# Sheet1.net
KiCad netlist of a schematic drawn in Altium Designer
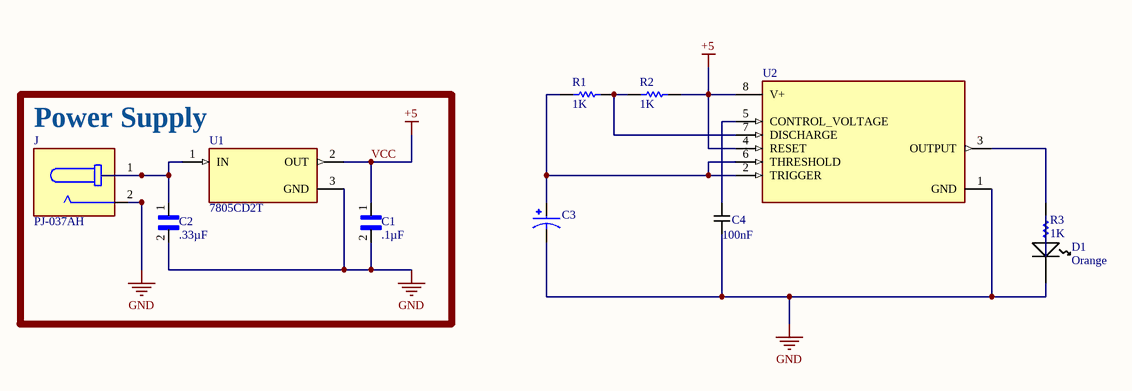
[diagram p0: Sheet1.SchDoc]

(export (version "E")
  (design (tool "Eeschema 10.0.6"))
  (components
    (comp (ref "C1")
      (value ".1µF")
      (footprint "CAPC3216X190N")
      (description "SMD Multilayer Ceramic Capacitor, GRM Series, 220 F, 20%, X5R, 6.3 V, 1206 [3216 Metric]")
      (fields (field (name "DIGI-KEY_PART_NUMBER") "490-13970-1-ND") (field (name "MP") "GRM31CR60J227ME11L"))
      (libsource (lib "GRM31CR60J227ME11L") (part "GRM31CR60J227ME11L"))
    )
    (comp (ref "C2")
      (value ".33µF")
      (footprint "CAPC3216X190N")
      (description "SMD Multilayer Ceramic Capacitor, GRM Series, 220 F, 20%, X5R, 6.3 V, 1206 [3216 Metric]")
      (fields (field (name "DIGI-KEY_PART_NUMBER") "490-13970-1-ND") (field (name "MP") "GRM31CR60J227ME11L"))
      (libsource (lib "GRM31CR60J227ME11L") (part "GRM31CR60J227ME11L"))
    )
    (comp (ref "C3")
      (value "EEUED2G100")
      (footprint "CAPPRD500W60D1000H2000")
      (description "10F 400V Aluminum Electrolytic Capacitors Radial, Can 8000 Hrs @ 105C")
      (fields (field (name "MF") "Panasonic Electronic") (field (name "MP") "EEU-ED2G100"))
      (libsource (lib "EEUED2G100") (part "EEUED2G100"))
    )
    (comp (ref "C4")
      (value "100nF Ceramic Multilayer Capacitor_1")
      (footprint "CAPCP2012X09N")
      (description "AVX 0805 Standard 100nF Ceramic Multilayer Capacitor, 50 V dc X7R Dielectric ±10% SMD")
      (fields
        (field (name "MANUFACTURER") "AVX")
        (field (name "VOLTAGE") "50V")
        (field (name "CAPACITANCE") "100nF")
        (field (name "CREATOR") "Ritesh Kanjee")
      )
      (libsource (lib "RS Components - Capacitors") (part "100nF Ceramic Multilayer Capacitor_1"))
    )
    (comp (ref "D1")
      (value "Kingbright Orange LED, 200 mcd 120 ° 0805")
      (footprint "LED1913X12NYEL/ORANGE")
      (fields
        (field (name "MANUFACTURER") "KingBright")
        (field (name "MANUFACTURER PART NO.") "KP-2012SEC")
        (field (name "COLOR") "Orange")
        (field (name "CREATOR") "Ritesh Kanjee")
      )
      (libsource (lib "KingBright LEDs") (part "Kingbright Orange LED, 200 mcd 120 ° 0805"))
    )
    (comp (ref "J")
      (value "PJ-037AH")
      (footprint "CUI_PJ-037AH")
      (description "2.0 x 6.5 mm, 5.0 A, Horizontal, Through Hole, Dc Power Jack Connector")
      (fields (field (name "MF") "CUI Devices"))
      (libsource (lib "PJ-037AH") (part "PJ-037AH"))
    )
    (comp (ref "R1")
      (value "1K")
      (footprint "RES_ERJS03F1001V")
      (description "Resistor")
      (libsource (lib "Simulation Generic Components") (part "Resistor"))
    )
    (comp (ref "R2")
      (value "1K")
      (footprint "RES_ERJS03F1001V")
      (description "Resistor")
      (libsource (lib "Simulation Generic Components") (part "Resistor"))
    )
    (comp (ref "R3")
      (value "1K")
      (footprint "RES_ERJS03F1001V")
      (description "Resistor")
      (libsource (lib "Simulation Generic Components") (part "Resistor"))
    )
    (comp (ref "U1")
      (value "7805CD2T")
      (footprint "TO254P1542X460-3N")
      (description "Linear Voltage Regulator IC Positive Fixed 1 Output 1.5A D2PAK")
      (fields (field (name "MF") "STMicroelectronics"))
      (libsource (lib "7805CD2T") (part "7805CD2T"))
    )
    (comp (ref "U2")
      (value "LM555CM/NOPB")
      (footprint "SOIC127P599X175-8N")
      (description "Highly Stable 555 Timer")
      (fields (field (name "MF") "Texas Instruments"))
      (libsource (lib "LM555CM_NOPB") (part "LM555CM/NOPB"))
    )
  )
  (nets
    (net (code "1") (name "+5") (class "Default")
      (node (ref "C1") (pin "1") (pinfunction "1_1") (pintype "passive"))
      (node (ref "R2") (pin "1") (pinfunction "1_1") (pintype "passive"))
      (node (ref "U1") (pin "2") (pinfunction "OUT_2") (pintype "output"))
      (node (ref "U2") (pin "4") (pinfunction "RESET_4") (pintype "input"))
      (node (ref "U2") (pin "8") (pinfunction "V+_8") (pintype "power_in"))
    )
    (net (code "2") (name "GND") (class "Default")
      (node (ref "C1") (pin "2") (pinfunction "2_2") (pintype "passive"))
      (node (ref "C2") (pin "2") (pinfunction "2_2") (pintype "passive"))
      (node (ref "C3") (pin "N") (pinfunction "N_N") (pintype "passive"))
      (node (ref "C4") (pin "1") (pinfunction "1_1") (pintype "passive"))
      (node (ref "D1") (pin "2") (pinfunction "K_2") (pintype "passive"))
      (node (ref "J") (pin "2") (pinfunction "2_2") (pintype "passive"))
      (node (ref "U1") (pin "3") (pinfunction "GND_3") (pintype "power_in"))
      (node (ref "U2") (pin "1") (pinfunction "GND_1") (pintype "power_in"))
    )
    (net (code "3") (name "Net-(D1-A)") (class "Default")
      (node (ref "D1") (pin "1") (pinfunction "A_1") (pintype "passive"))
      (node (ref "R3") (pin "1") (pinfunction "1_1") (pintype "passive"))
    )
    (net (code "4") (name "Net-(U1-IN)") (class "Default")
      (node (ref "C2") (pin "1") (pinfunction "1_1") (pintype "passive"))
      (node (ref "J") (pin "1") (pinfunction "1_1") (pintype "passive"))
      (node (ref "U1") (pin "1") (pinfunction "IN_1") (pintype "input"))
    )
    (net (code "5") (name "Net-(U2-CONTROL_VOLTAGE)") (class "Default")
      (node (ref "C4") (pin "2") (pinfunction "2_2") (pintype "passive"))
      (node (ref "U2") (pin "5") (pinfunction "CONTROL_VOLTAGE_5") (pintype "input"))
    )
    (net (code "6") (name "Net-(U2-DISCHARGE)") (class "Default")
      (node (ref "R1") (pin "2") (pinfunction "2_2") (pintype "passive"))
      (node (ref "R2") (pin "2") (pinfunction "2_2") (pintype "passive"))
      (node (ref "U2") (pin "7") (pinfunction "DISCHARGE_7") (pintype "input"))
    )
    (net (code "7") (name "Net-(U2-OUTPUT)") (class "Default")
      (node (ref "R3") (pin "2") (pinfunction "2_2") (pintype "passive"))
      (node (ref "U2") (pin "3") (pinfunction "OUTPUT_3") (pintype "output"))
    )
    (net (code "8") (name "Net-(U2-THRESHOLD)") (class "Default")
      (node (ref "C3") (pin "P") (pinfunction "P_P") (pintype "passive"))
      (node (ref "R1") (pin "1") (pinfunction "1_1") (pintype "passive"))
      (node (ref "U2") (pin "2") (pinfunction "TRIGGER_2") (pintype "input"))
      (node (ref "U2") (pin "6") (pinfunction "THRESHOLD_6") (pintype "input"))
    )
  )
)
